# RotaryEncoder_Breakout_4ch.net
KiCad netlist of a schematic drawn in EAGLE
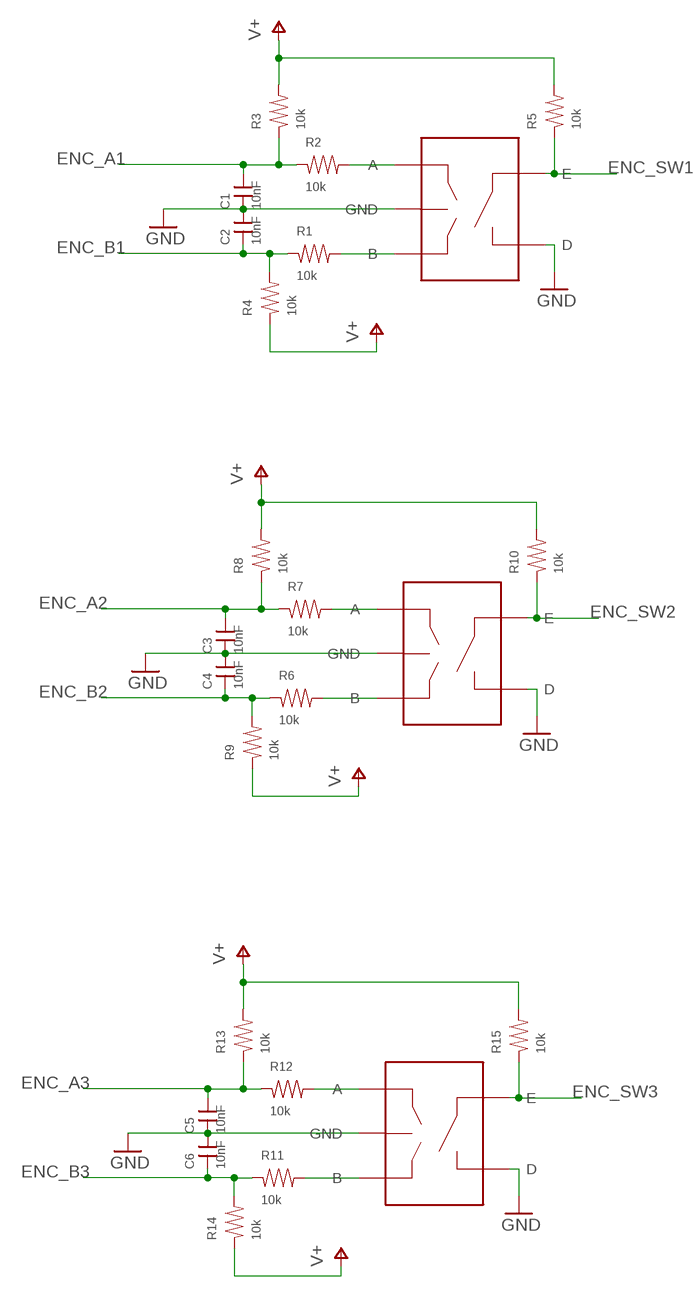
[diagram p0: schematic, sheet 1]

(export (version "E")
  (design (tool "Eeschema 10.0.6"))
  (components
    (comp (ref "C1")
      (value "10nF")
      (footprint "eagle-import:0603")
      (libsource (lib "eagle-import") (part "CAP0603"))
    )
    (comp (ref "C2")
      (value "10nF")
      (footprint "eagle-import:0603")
      (libsource (lib "eagle-import") (part "CAP0603"))
    )
    (comp (ref "C3")
      (value "10nF")
      (footprint "eagle-import:0603")
      (libsource (lib "eagle-import") (part "CAP0603"))
    )
    (comp (ref "C4")
      (value "10nF")
      (footprint "eagle-import:0603")
      (libsource (lib "eagle-import") (part "CAP0603"))
    )
    (comp (ref "C5")
      (value "10nF")
      (footprint "eagle-import:0603")
      (libsource (lib "eagle-import") (part "CAP0603"))
    )
    (comp (ref "C6")
      (value "10nF")
      (footprint "eagle-import:0603")
      (libsource (lib "eagle-import") (part "CAP0603"))
    )
    (comp (ref "ENC1")
      (value "PEC09")
      (footprint "eagle-import:PEC092320FS")
      (libsource (lib "eagle-import") (part "PEC09"))
    )
    (comp (ref "ENC2")
      (value "PEC09")
      (footprint "eagle-import:PEC092320FS")
      (libsource (lib "eagle-import") (part "PEC09"))
    )
    (comp (ref "ENC3")
      (value "PEC09")
      (footprint "eagle-import:PEC092320FS")
      (libsource (lib "eagle-import") (part "PEC09"))
    )
    (comp (ref "R1")
      (value "10k")
      (footprint "eagle-import:0603")
      (libsource (lib "eagle-import") (part "RES0603"))
    )
    (comp (ref "R2")
      (value "10k")
      (footprint "eagle-import:0603")
      (libsource (lib "eagle-import") (part "RES0603"))
    )
    (comp (ref "R3")
      (value "10k")
      (footprint "eagle-import:0603")
      (libsource (lib "eagle-import") (part "RES0603"))
    )
    (comp (ref "R4")
      (value "10k")
      (footprint "eagle-import:0603")
      (libsource (lib "eagle-import") (part "RES0603"))
    )
    (comp (ref "R5")
      (value "10k")
      (footprint "eagle-import:0603")
      (libsource (lib "eagle-import") (part "RES0603"))
    )
    (comp (ref "R6")
      (value "10k")
      (footprint "eagle-import:0603")
      (libsource (lib "eagle-import") (part "RES0603"))
    )
    (comp (ref "R7")
      (value "10k")
      (footprint "eagle-import:0603")
      (libsource (lib "eagle-import") (part "RES0603"))
    )
    (comp (ref "R8")
      (value "10k")
      (footprint "eagle-import:0603")
      (libsource (lib "eagle-import") (part "RES0603"))
    )
    (comp (ref "R9")
      (value "10k")
      (footprint "eagle-import:0603")
      (libsource (lib "eagle-import") (part "RES0603"))
    )
    (comp (ref "R10")
      (value "10k")
      (footprint "eagle-import:0603")
      (libsource (lib "eagle-import") (part "RES0603"))
    )
    (comp (ref "R11")
      (value "10k")
      (footprint "eagle-import:0603")
      (libsource (lib "eagle-import") (part "RES0603"))
    )
    (comp (ref "R12")
      (value "10k")
      (footprint "eagle-import:0603")
      (libsource (lib "eagle-import") (part "RES0603"))
    )
    (comp (ref "R13")
      (value "10k")
      (footprint "eagle-import:0603")
      (libsource (lib "eagle-import") (part "RES0603"))
    )
    (comp (ref "R14")
      (value "10k")
      (footprint "eagle-import:0603")
      (libsource (lib "eagle-import") (part "RES0603"))
    )
    (comp (ref "R15")
      (value "10k")
      (footprint "eagle-import:0603")
      (libsource (lib "eagle-import") (part "RES0603"))
    )
  )
  (nets
    (net (code "1") (name "/ENC_A1") (class "Default")
      (node (ref "C1") (pin "2") (pinfunction "P$2_2") (pintype "passive"))
      (node (ref "R2") (pin "1") (pinfunction "P$1_1") (pintype "passive"))
      (node (ref "R3") (pin "1") (pinfunction "P$1_1") (pintype "passive"))
    )
    (net (code "2") (name "/ENC_A2") (class "Default")
      (node (ref "C3") (pin "2") (pinfunction "P$2_2") (pintype "passive"))
      (node (ref "R7") (pin "1") (pinfunction "P$1_1") (pintype "passive"))
      (node (ref "R8") (pin "1") (pinfunction "P$1_1") (pintype "passive"))
    )
    (net (code "3") (name "/ENC_A3") (class "Default")
      (node (ref "C5") (pin "2") (pinfunction "P$2_2") (pintype "passive"))
      (node (ref "R12") (pin "1") (pinfunction "P$1_1") (pintype "passive"))
      (node (ref "R13") (pin "1") (pinfunction "P$1_1") (pintype "passive"))
    )
    (net (code "4") (name "/ENC_B1") (class "Default")
      (node (ref "C2") (pin "1") (pinfunction "P$1_1") (pintype "passive"))
      (node (ref "R1") (pin "1") (pinfunction "P$1_1") (pintype "passive"))
      (node (ref "R4") (pin "2") (pinfunction "P$2_2") (pintype "passive"))
    )
    (net (code "5") (name "/ENC_B2") (class "Default")
      (node (ref "C4") (pin "1") (pinfunction "P$1_1") (pintype "passive"))
      (node (ref "R6") (pin "1") (pinfunction "P$1_1") (pintype "passive"))
      (node (ref "R9") (pin "2") (pinfunction "P$2_2") (pintype "passive"))
    )
    (net (code "6") (name "/ENC_B3") (class "Default")
      (node (ref "C6") (pin "1") (pinfunction "P$1_1") (pintype "passive"))
      (node (ref "R11") (pin "1") (pinfunction "P$1_1") (pintype "passive"))
      (node (ref "R14") (pin "2") (pinfunction "P$2_2") (pintype "passive"))
    )
    (net (code "7") (name "/ENC_SW1") (class "Default")
      (node (ref "ENC1") (pin "E") (pinfunction "E_E") (pintype "bidirectional"))
      (node (ref "R5") (pin "1") (pinfunction "P$1_1") (pintype "passive"))
    )
    (net (code "8") (name "/ENC_SW2") (class "Default")
      (node (ref "ENC2") (pin "E") (pinfunction "E_E") (pintype "bidirectional"))
      (node (ref "R10") (pin "1") (pinfunction "P$1_1") (pintype "passive"))
    )
    (net (code "9") (name "/ENC_SW3") (class "Default")
      (node (ref "ENC3") (pin "E") (pinfunction "E_E") (pintype "bidirectional"))
      (node (ref "R15") (pin "1") (pinfunction "P$1_1") (pintype "passive"))
    )
    (net (code "10") (name "GND") (class "Default")
      (node (ref "C1") (pin "1") (pinfunction "P$1_1") (pintype "passive"))
      (node (ref "C2") (pin "2") (pinfunction "P$2_2") (pintype "passive"))
      (node (ref "C3") (pin "1") (pinfunction "P$1_1") (pintype "passive"))
      (node (ref "C4") (pin "2") (pinfunction "P$2_2") (pintype "passive"))
      (node (ref "C5") (pin "1") (pinfunction "P$1_1") (pintype "passive"))
      (node (ref "C6") (pin "2") (pinfunction "P$2_2") (pintype "passive"))
      (node (ref "ENC1") (pin "C") (pinfunction "GND_C") (pintype "bidirectional"))
      (node (ref "ENC1") (pin "D") (pinfunction "D_D") (pintype "bidirectional"))
      (node (ref "ENC2") (pin "C") (pinfunction "GND_C") (pintype "bidirectional"))
      (node (ref "ENC2") (pin "D") (pinfunction "D_D") (pintype "bidirectional"))
      (node (ref "ENC3") (pin "C") (pinfunction "GND_C") (pintype "bidirectional"))
      (node (ref "ENC3") (pin "D") (pinfunction "D_D") (pintype "bidirectional"))
    )
    (net (code "11") (name "Net-(R1-P$2)") (class "Default")
      (node (ref "ENC1") (pin "B") (pinfunction "B_B") (pintype "bidirectional"))
      (node (ref "R1") (pin "2") (pinfunction "P$2_2") (pintype "passive"))
    )
    (net (code "12") (name "Net-(R2-P$2)") (class "Default")
      (node (ref "ENC1") (pin "A") (pinfunction "A_A") (pintype "bidirectional"))
      (node (ref "R2") (pin "2") (pinfunction "P$2_2") (pintype "passive"))
    )
    (net (code "13") (name "Net-(R6-P$2)") (class "Default")
      (node (ref "ENC2") (pin "B") (pinfunction "B_B") (pintype "bidirectional"))
      (node (ref "R6") (pin "2") (pinfunction "P$2_2") (pintype "passive"))
    )
    (net (code "14") (name "Net-(R7-P$2)") (class "Default")
      (node (ref "ENC2") (pin "A") (pinfunction "A_A") (pintype "bidirectional"))
      (node (ref "R7") (pin "2") (pinfunction "P$2_2") (pintype "passive"))
    )
    (net (code "15") (name "Net-(R11-P$2)") (class "Default")
      (node (ref "ENC3") (pin "B") (pinfunction "B_B") (pintype "bidirectional"))
      (node (ref "R11") (pin "2") (pinfunction "P$2_2") (pintype "passive"))
    )
    (net (code "16") (name "Net-(R12-P$2)") (class "Default")
      (node (ref "ENC3") (pin "A") (pinfunction "A_A") (pintype "bidirectional"))
      (node (ref "R12") (pin "2") (pinfunction "P$2_2") (pintype "passive"))
    )
    (net (code "17") (name "V+") (class "Default")
      (node (ref "R10") (pin "2") (pinfunction "P$2_2") (pintype "passive"))
      (node (ref "R13") (pin "2") (pinfunction "P$2_2") (pintype "passive"))
      (node (ref "R14") (pin "1") (pinfunction "P$1_1") (pintype "passive"))
      (node (ref "R15") (pin "2") (pinfunction "P$2_2") (pintype "passive"))
      (node (ref "R3") (pin "2") (pinfunction "P$2_2") (pintype "passive"))
      (node (ref "R4") (pin "1") (pinfunction "P$1_1") (pintype "passive"))
      (node (ref "R5") (pin "2") (pinfunction "P$2_2") (pintype "passive"))
      (node (ref "R8") (pin "2") (pinfunction "P$2_2") (pintype "passive"))
      (node (ref "R9") (pin "1") (pinfunction "P$1_1") (pintype "passive"))
    )
  )
)
